# NG2092_IMU.net
KiCad netlist of a schematic drawn in Altium Designer
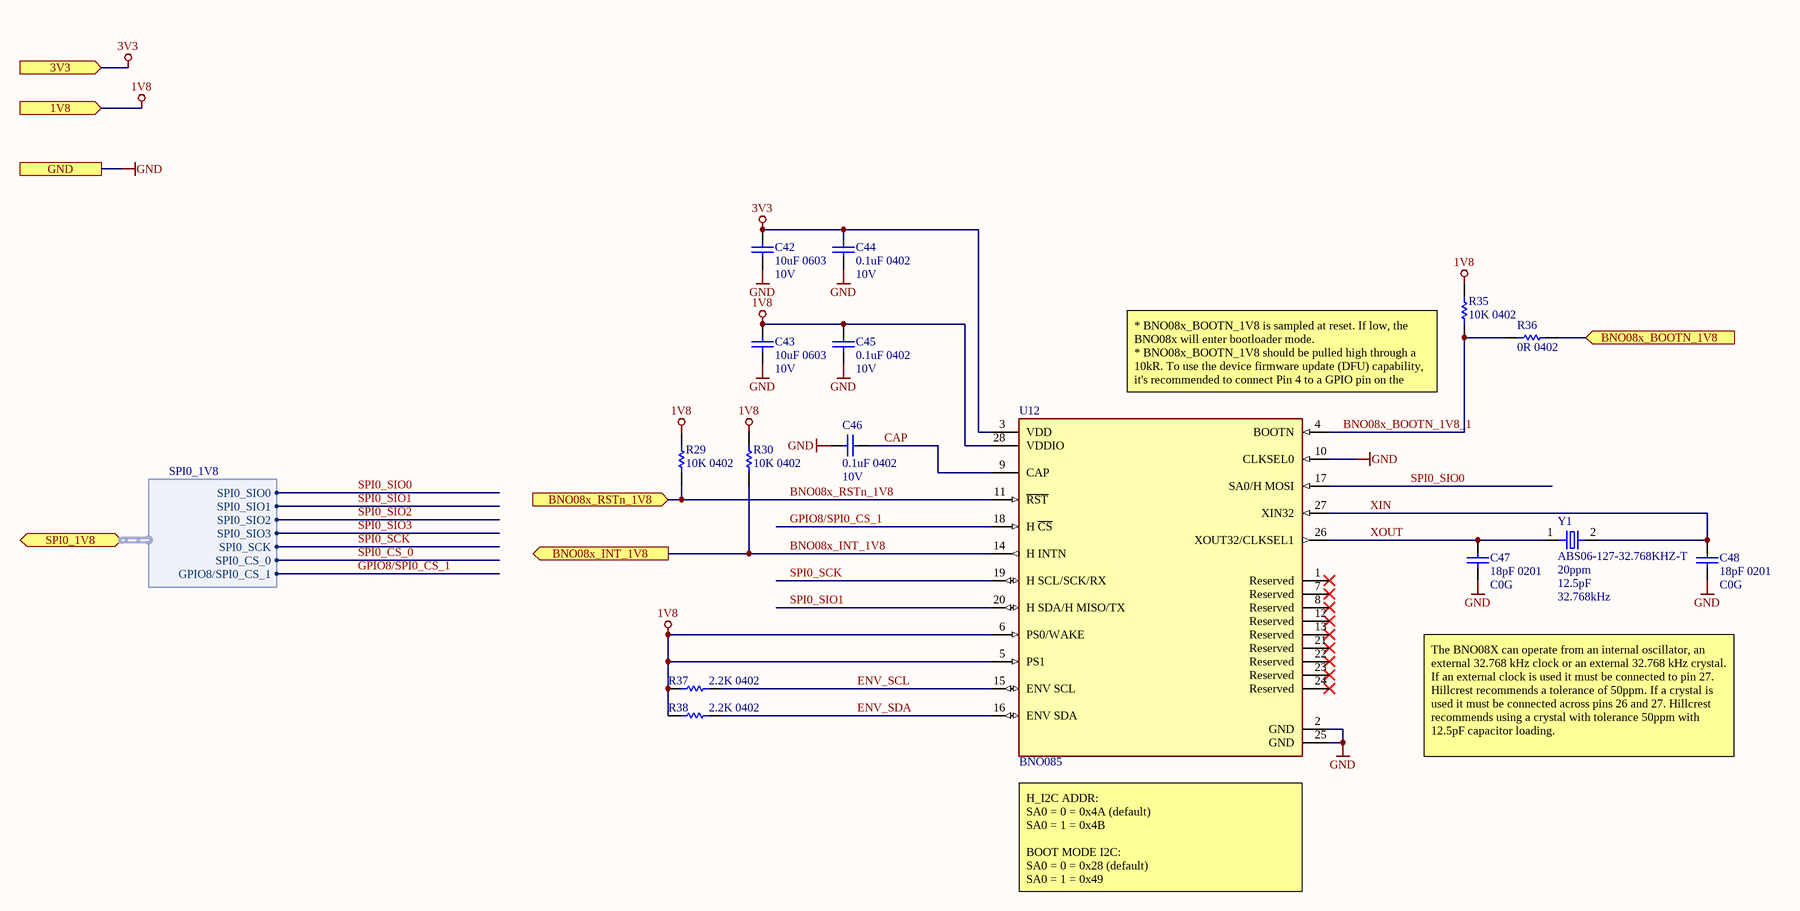
[diagram p0: NG2092_IMU.SchDoc]

(export (version "E")
  (design (tool "Eeschema 10.0.6"))
  (components
    (comp (ref "C42")
      (value "10uF 0603")
      (footprint "CAP_Altium_Vault_Generic:CAPC0603(1608)100_L")
      (description "CAP CER 10UF 10V X5R 0603 20%")
      (fields (field (name "TOLERANCE") "20%") (field (name "VOLTAGE RATING") "10V"))
      (libsource (lib "LuxonisMaster") (part "GRM188R61A106ME69D"))
    )
    (comp (ref "C43")
      (value "10uF 0603")
      (footprint "CAP_Altium_Vault_Generic:CAPC0603(1608)100_L")
      (description "CAP CER 10UF 10V X5R 0603 20%")
      (fields (field (name "TOLERANCE") "20%") (field (name "VOLTAGE RATING") "10V"))
      (libsource (lib "LuxonisMaster") (part "GRM188R61A106ME69D"))
    )
    (comp (ref "C44")
      (value "0.1uF 0402")
      (footprint "CAP_Altium_Vault_Generic:CAPC0402(1005)70_L")
      (description "CAP CER 0.1UF 10V X7R 0402 5%")
      (fields (field (name "TOLERANCE") "5%") (field (name "VOLTAGE RATING") "10V"))
      (libsource (lib "LuxonisMaster") (part "GRM155R71A104JA01D"))
    )
    (comp (ref "C45")
      (value "0.1uF 0402")
      (footprint "CAP_Altium_Vault_Generic:CAPC0402(1005)70_L")
      (description "CAP CER 0.1UF 10V X7R 0402 5%")
      (fields (field (name "TOLERANCE") "5%") (field (name "VOLTAGE RATING") "10V"))
      (libsource (lib "LuxonisMaster") (part "GRM155R71A104JA01D"))
    )
    (comp (ref "C46")
      (value "0.1uF 0402")
      (footprint "CAP_Altium_Vault_Generic:CAPC0402(1005)70_L")
      (description "CAP CER 0.1UF 10V X7R 0402 5%")
      (fields (field (name "TOLERANCE") "5%") (field (name "VOLTAGE RATING") "10V"))
      (libsource (lib "LuxonisMaster") (part "GRM155R71A104JA01D"))
    )
    (comp (ref "C47")
      (value "18pF 0201")
      (footprint "CAP_Altium_Vault_Generic:CAPC0201(0603)33_N")
      (description "Cap Ceramic 18pF 25V C0G 1% Pad SMD 0201 125C T/R")
      (fields (field (name "TOLERANCE") "1%") (field (name "DIELECTRIC") "C0G"))
      (libsource (lib "DM1092_R0M0E0") (part "GRM0335C1E180FA01D"))
    )
    (comp (ref "C48")
      (value "18pF 0201")
      (footprint "CAP_Altium_Vault_Generic:CAPC0201(0603)33_N")
      (description "Cap Ceramic 18pF 25V C0G 1% Pad SMD 0201 125C T/R")
      (fields (field (name "TOLERANCE") "1%") (field (name "DIELECTRIC") "C0G"))
      (libsource (lib "DM1092_R0M0E0") (part "GRM0335C1E180FA01D"))
    )
    (comp (ref "R29")
      (value "10K 0402")
      (footprint "RES_Altium_Vault_Generic:RESC0402(1005)_L")
      (fields (field (name "TOLERANCE") "1%"))
      (libsource (lib "LuxonisMaster") (part "RC0402FR-1310KL"))
    )
    (comp (ref "R30")
      (value "10K 0402")
      (footprint "RES_Altium_Vault_Generic:RESC0402(1005)_L")
      (fields (field (name "TOLERANCE") "1%"))
      (libsource (lib "LuxonisMaster") (part "RC0402FR-1310KL"))
    )
    (comp (ref "R35")
      (value "10K 0402")
      (footprint "RES_Altium_Vault_Generic:RESC0402(1005)_L")
      (fields (field (name "TOLERANCE") "1%"))
      (libsource (lib "LuxonisMaster") (part "RC0402FR-1310KL"))
    )
    (comp (ref "R36")
      (value "0R 0402")
      (footprint "RES_Altium_Vault_Generic:RESC0402(1005)_L")
      (description "RES SMD 0 OHM JUMPER 1/16W 0402")
      (fields (field (name "TOLERANCE") "5%"))
      (libsource (lib "LuxonisMaster") (part "CRCW04020000Z0ED"))
    )
    (comp (ref "R37")
      (value "2.2K 0402")
      (footprint "RES_Altium_Vault_Generic:RESC0402(1005)_N")
      (description "RES SMD 2.2K OHM 1% 1/16W 0402")
      (fields (field (name "TOLERANCE") "1%"))
      (libsource (lib "LuxonisMaster") (part "RC0402FR-072K2L"))
    )
    (comp (ref "R38")
      (value "2.2K 0402")
      (footprint "RES_Altium_Vault_Generic:RESC0402(1005)_N")
      (description "RES SMD 2.2K OHM 1% 1/16W 0402")
      (fields (field (name "TOLERANCE") "1%"))
      (libsource (lib "LuxonisMaster") (part "RC0402FR-072K2L"))
    )
    (comp (ref "U12")
      (value "BNO085")
      (footprint "BNO085")
      (description "IMU ACCEL/GYRO/MAG I2C 32BIT")
      (libsource (lib "NG2092") (part "BNO085"))
    )
    (comp (ref "Y1")
      (value "ABS06-127-32.768KHZ-T")
      (footprint "ABS06-127-32.768KHZ-T")
      (description "CRYSTAL 32.768kHz ±20ppm Crystal 12.5pF 90 kOhms 2-SMD, No Lead")
      (fields
        (field (name "FREQUENCY TOLERANCE") "20ppm")
        (field (name "LOAD CAPACITANCE") "12.5pF")
        (field (name "FREQUENCY") "32.768kHz")
      )
      (libsource (lib "NG2092") (part "ABS06-127-32.768KHZ-T"))
    )
  )
  (nets
    (net (code "2") (name "/BNO08x_BOOTN_1V8") (class "Default")
      (node (ref "R36") (pin "1") (pinfunction "1_1") (pintype "passive"))
    )
    (net (code "3") (name "/BNO08x_BOOTN_1V8_1") (class "Default")
      (node (ref "R35") (pin "1") (pinfunction "1_1") (pintype "passive"))
      (node (ref "R36") (pin "2") (pinfunction "2_2") (pintype "passive"))
      (node (ref "U12") (pin "4") (pinfunction "BOOTN_4") (pintype "input"))
    )
    (net (code "4") (name "/BNO08x_INT_1V8") (class "Default")
      (node (ref "R30") (pin "1") (pinfunction "1_1") (pintype "passive"))
      (node (ref "U12") (pin "14") (pinfunction "H_INTN_14") (pintype "output"))
    )
    (net (code "5") (name "/BNO08x_RSTn_1V8") (class "Default")
      (node (ref "R29") (pin "1") (pinfunction "1_1") (pintype "passive"))
      (node (ref "U12") (pin "11") (pinfunction "~{RST}_11") (pintype "input"))
    )
    (net (code "6") (name "/CAP") (class "Default")
      (node (ref "C46") (pin "1") (pinfunction "1_1") (pintype "passive"))
      (node (ref "U12") (pin "9") (pinfunction "CAP_9") (pintype "passive"))
    )
    (net (code "7") (name "/ENV_SCL") (class "Default")
      (node (ref "R37") (pin "2") (pinfunction "2_2") (pintype "passive"))
      (node (ref "U12") (pin "15") (pinfunction "ENV_SCL_15") (pintype "bidirectional"))
    )
    (net (code "8") (name "/ENV_SDA") (class "Default")
      (node (ref "R38") (pin "2") (pinfunction "2_2") (pintype "passive"))
      (node (ref "U12") (pin "16") (pinfunction "ENV_SDA_16") (pintype "bidirectional"))
    )
    (net (code "9") (name "/GPIO8{slash}SPI0_CS_1") (class "Default")
      (node (ref "U12") (pin "18") (pinfunction "H_~{CS}_18") (pintype "input"))
    )
    (net (code "11") (name "/SPI0_SCK") (class "Default")
      (node (ref "U12") (pin "19") (pinfunction "H_SCL/SCK/RX_19") (pintype "bidirectional"))
    )
    (net (code "12") (name "/SPI0_SIO0") (class "Default")
      (node (ref "U12") (pin "17") (pinfunction "SA0/H_MOSI_17") (pintype "input"))
    )
    (net (code "13") (name "/SPI0_SIO1") (class "Default")
      (node (ref "U12") (pin "20") (pinfunction "H_SDA/H_MISO/TX_20") (pintype "bidirectional"))
    )
    (net (code "16") (name "/XIN") (class "Default")
      (node (ref "C48") (pin "2") (pinfunction "2_2") (pintype "passive"))
      (node (ref "U12") (pin "27") (pinfunction "XIN32_27") (pintype "input"))
      (node (ref "Y1") (pin "2") (pinfunction "2_2") (pintype "passive"))
    )
    (net (code "17") (name "/XOUT") (class "Default")
      (node (ref "C47") (pin "2") (pinfunction "2_2") (pintype "passive"))
      (node (ref "U12") (pin "26") (pinfunction "XOUT32/CLKSEL1_26") (pintype "output"))
      (node (ref "Y1") (pin "1") (pinfunction "1_1") (pintype "passive"))
    )
    (net (code "19") (name "1V8") (class "Default")
      (node (ref "C43") (pin "2") (pinfunction "2_2") (pintype "passive"))
      (node (ref "C45") (pin "2") (pinfunction "2_2") (pintype "passive"))
      (node (ref "R29") (pin "2") (pinfunction "2_2") (pintype "passive"))
      (node (ref "R30") (pin "2") (pinfunction "2_2") (pintype "passive"))
      (node (ref "R35") (pin "2") (pinfunction "2_2") (pintype "passive"))
      (node (ref "R37") (pin "1") (pinfunction "1_1") (pintype "passive"))
      (node (ref "R38") (pin "1") (pinfunction "1_1") (pintype "passive"))
      (node (ref "U12") (pin "28") (pinfunction "VDDIO_28") (pintype "power_in"))
      (node (ref "U12") (pin "5") (pinfunction "PS1_5") (pintype "input"))
      (node (ref "U12") (pin "6") (pinfunction "PS0/WAKE_6") (pintype "input"))
    )
    (net (code "20") (name "3V3") (class "Default")
      (node (ref "C42") (pin "2") (pinfunction "2_2") (pintype "passive"))
      (node (ref "C44") (pin "2") (pinfunction "2_2") (pintype "passive"))
      (node (ref "U12") (pin "3") (pinfunction "VDD_3") (pintype "power_in"))
    )
    (net (code "21") (name "GND") (class "Default")
      (node (ref "C42") (pin "1") (pinfunction "1_1") (pintype "passive"))
      (node (ref "C43") (pin "1") (pinfunction "1_1") (pintype "passive"))
      (node (ref "C44") (pin "1") (pinfunction "1_1") (pintype "passive"))
      (node (ref "C45") (pin "1") (pinfunction "1_1") (pintype "passive"))
      (node (ref "C46") (pin "2") (pinfunction "2_2") (pintype "passive"))
      (node (ref "C47") (pin "1") (pinfunction "1_1") (pintype "passive"))
      (node (ref "C48") (pin "1") (pinfunction "1_1") (pintype "passive"))
      (node (ref "U12") (pin "10") (pinfunction "CLKSEL0_10") (pintype "input"))
      (node (ref "U12") (pin "2") (pinfunction "GND_2") (pintype "power_in"))
      (node (ref "U12") (pin "25") (pinfunction "GND_25") (pintype "power_in"))
    )
    (net (code "22") (name "unconnected-(U12-Reserved-Pad1)") (class "Default")
      (node (ref "U12") (pin "1") (pinfunction "Reserved_1") (pintype "passive+no_connect"))
    )
    (net (code "23") (name "unconnected-(U12-Reserved-Pad7)") (class "Default")
      (node (ref "U12") (pin "7") (pinfunction "Reserved_7") (pintype "passive+no_connect"))
    )
    (net (code "24") (name "unconnected-(U12-Reserved-Pad8)") (class "Default")
      (node (ref "U12") (pin "8") (pinfunction "Reserved_8") (pintype "passive+no_connect"))
    )
    (net (code "25") (name "unconnected-(U12-Reserved-Pad12)") (class "Default")
      (node (ref "U12") (pin "12") (pinfunction "Reserved_12") (pintype "passive+no_connect"))
    )
    (net (code "26") (name "unconnected-(U12-Reserved-Pad13)") (class "Default")
      (node (ref "U12") (pin "13") (pinfunction "Reserved_13") (pintype "passive+no_connect"))
    )
    (net (code "27") (name "unconnected-(U12-Reserved-Pad21)") (class "Default")
      (node (ref "U12") (pin "21") (pinfunction "Reserved_21") (pintype "passive+no_connect"))
    )
    (net (code "28") (name "unconnected-(U12-Reserved-Pad22)") (class "Default")
      (node (ref "U12") (pin "22") (pinfunction "Reserved_22") (pintype "passive+no_connect"))
    )
    (net (code "29") (name "unconnected-(U12-Reserved-Pad23)") (class "Default")
      (node (ref "U12") (pin "23") (pinfunction "Reserved_23") (pintype "passive+no_connect"))
    )
    (net (code "30") (name "unconnected-(U12-Reserved-Pad24)") (class "Default")
      (node (ref "U12") (pin "24") (pinfunction "Reserved_24") (pintype "passive+no_connect"))
    )
  )
)
